# Power.net
KiCad netlist of a schematic drawn in Altium Designer
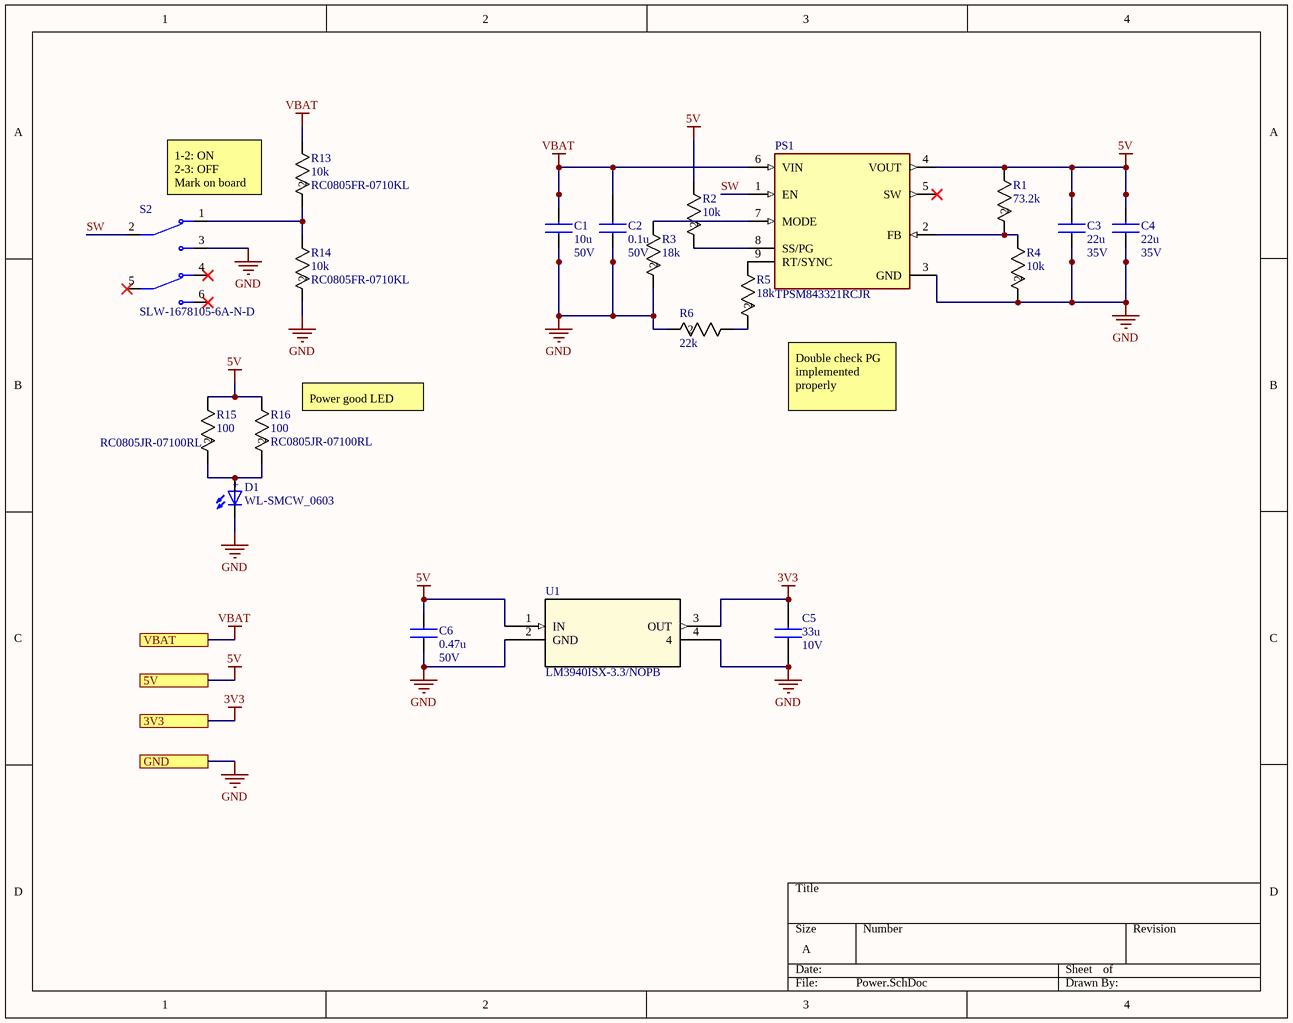
[diagram p0: Power.SchDoc]

(export (version "E")
  (design (tool "Eeschema 10.0.6"))
  (components
    (comp (ref "C1")
      (value "10u")
      (footprint "CAPC2012X145N")
      (description "Multilayer Ceramic Chip Capacitors, Capacitance=10?F, LxWxT:2x1.25x1.25mm")
      (fields
        (field (name "MOUSER PART NUMBER") "810-C2012X5R1H106K12")
        (field (name "MANUFACTURER_PART_NUMBER") "C2012X5R1H106K125AC")
        (field (name "RATED VOLTAGE") "50V")
      )
      (libsource (lib "Caps") (part "C2012X5R1H106K125AC"))
    )
    (comp (ref "C2")
      (value "0.1u")
      (footprint "CAPC2012X145N")
      (description "Multilayer Ceramic Chip Capacitors, Capacitance=0.1u")
      (fields
        (field (name "MANUFACTURER_PART_NUMBER") "KAM21BR71H104JM")
        (field (name "RATED VOLTAGE") "50V")
      )
      (libsource (lib "Caps") (part "KAM21BR71H104JM"))
    )
    (comp (ref "C3")
      (value "22u")
      (footprint "CAPC2012X145N")
      (description "Multilayer Ceramic Chip Capacitors, Capacitance=22u")
      (fields
        (field (name "MANUFACTURER_PART_NUMBER") "C2012X5R1V226M125AC")
        (field (name "RATED VOLTAGE") "35V")
      )
      (libsource (lib "Caps") (part "C2012X5R1V226M125AC"))
    )
    (comp (ref "C4")
      (value "22u")
      (footprint "CAPC2012X145N")
      (description "Multilayer Ceramic Chip Capacitors, Capacitance=22u")
      (fields
        (field (name "MANUFACTURER_PART_NUMBER") "C2012X5R1V226M125AC")
        (field (name "RATED VOLTAGE") "35V")
      )
      (libsource (lib "Caps") (part "C2012X5R1V226M125AC"))
    )
    (comp (ref "C5")
      (value "33u")
      (footprint "CAPC2012X145N")
      (description "Multilayer Ceramic Chip Capacitors, Capacitance=33u")
      (fields
        (field (name "MANUFACTURER_PART_NUMBER") "C2012X5R1A336M125AC")
        (field (name "RATED VOLTAGE") "10V")
      )
      (libsource (lib "Caps") (part "C2012X5R1A336M125AC"))
    )
    (comp (ref "C6")
      (value "0.47u")
      (footprint "CAPC2012X145N")
      (description "Multilayer Ceramic Chip Capacitors, Capacitance=0.47u")
      (fields
        (field (name "MANUFACTURER_PART_NUMBER") "GCM21BR71H474KA55K")
        (field (name "RATED VOLTAGE") "50V")
      )
      (libsource (lib "Caps") (part "GCM21BR71H474KA55K"))
    )
    (comp (ref "D1")
      (value "WL-SMCW_0603")
      (footprint "WL-SMCW_0603")
      (description "0603, Green Typ.(@20mA): 520nm, 430mcd, 3.2V, 140Â° InGaN")
      (fields (field (name "MF") "Wurth Electronics") (field (name "MP") "150060GS75000"))
      (libsource (lib "WL-SMCW_0603") (part "WL-SMCW_0603"))
    )
    (comp (ref "PS1")
      (value "TPSM843321RCJR")
      (footprint "MODULE_TPSM843321RCJR")
      (description "Non-Isolated PoL Module DC DC Converter 1 Output 5V 3A 3.8V - 18V Input")
      (fields (field (name "MF") "Texas Instruments"))
      (libsource (lib "TPSM843321RCJR") (part "TPSM843321RCJR"))
    )
    (comp (ref "R1")
      (value "73.2k")
      (footprint "RC0805N_YAG")
      (description "RES 0805 73.2k 1% 1/8W")
      (fields (field (name "MANUFACTURER_PART_NUMBER") "RC0805FR-0773K2L") (field (name "TOLERANCE") "1%"))
      (libsource (lib "Resistors") (part "RC0805FR-0773K2L"))
    )
    (comp (ref "R2")
      (value "10k")
      (footprint "RC0805N_YAG")
      (description "RES 0805 10k 1% 1/8W")
      (fields (field (name "MANUFACTURER_PART_NUMBER") "RC0805FR-0710KL") (field (name "TOLERANCE") "1%"))
      (libsource (lib "Resistors") (part "RC0805FR-0710KL"))
    )
    (comp (ref "R3")
      (value "18k")
      (footprint "RC0805N_YAG")
      (description "RES 0805 18k 1% 1/8W")
      (fields (field (name "MANUFACTURER_PART_NUMBER") "RC0805FR-0718KL") (field (name "TOLERANCE") "1%"))
      (libsource (lib "Resistors") (part "RC0805FR-0718KL"))
    )
    (comp (ref "R4")
      (value "10k")
      (footprint "RC0805N_YAG")
      (description "RES 0805 10k 1% 1/8W")
      (fields (field (name "MANUFACTURER_PART_NUMBER") "RC0805FR-0710KL") (field (name "TOLERANCE") "1%"))
      (libsource (lib "Resistors") (part "RC0805FR-0710KL"))
    )
    (comp (ref "R5")
      (value "18k")
      (footprint "RC0805N_YAG")
      (description "RES 0805 18k 1% 1/8W")
      (fields (field (name "MANUFACTURER_PART_NUMBER") "RC0805FR-0718KL") (field (name "TOLERANCE") "1%"))
      (libsource (lib "Resistors") (part "RC0805FR-0718KL"))
    )
    (comp (ref "R6")
      (value "22k")
      (footprint "RC0805N_YAG")
      (description "RES 0805 22k 1% 1/8W")
      (fields (field (name "MANUFACTURER_PART_NUMBER") "RC0805FR-0722KL") (field (name "TOLERANCE") "1%"))
      (libsource (lib "Resistors") (part "RC0805FR-0722KL"))
    )
    (comp (ref "R13")
      (value "RC0805FR-0710KL")
      (footprint "RC0805N_YAG")
      (description "RES 0805 10k 1% 1/8W")
      (fields (field (name "TOLERANCE") "1%") (field (name "ALTIUM_VALUE") "10k"))
      (libsource (lib "Resistors") (part "RC0805FR-0710KL"))
    )
    (comp (ref "R14")
      (value "RC0805FR-0710KL")
      (footprint "RC0805N_YAG")
      (description "RES 0805 10k 1% 1/8W")
      (fields (field (name "TOLERANCE") "1%") (field (name "ALTIUM_VALUE") "10k"))
      (libsource (lib "Resistors") (part "RC0805FR-0710KL"))
    )
    (comp (ref "R15")
      (value "RC0805JR-07100RL")
      (footprint "RC0805N_YAG")
      (description "RES 0805 100 5% 1/8W")
      (fields (field (name "TOLERANCE") "5%") (field (name "ALTIUM_VALUE") "100"))
      (libsource (lib "Resistors") (part "RC0805JR-07100RL"))
    )
    (comp (ref "R16")
      (value "RC0805JR-07100RL")
      (footprint "RC0805N_YAG")
      (description "RES 0805 100 5% 1/8W")
      (fields (field (name "TOLERANCE") "5%") (field (name "ALTIUM_VALUE") "100"))
      (libsource (lib "Resistors") (part "RC0805JR-07100RL"))
    )
    (comp (ref "S2")
      (value "SLW-1678105-6A-N-D")
      (footprint "SW_SLW-1678105-6A-N-D")
      (description "16 x 7.8 x 10.5 mm, 6 mm Raised Slide Actuator, Through Hole, Slide Switch")
      (fields (field (name "MF") "Same Sky"))
      (libsource (lib "SLW-1678105-6A-N-D") (part "SLW-1678105-6A-N-D"))
    )
    (comp (ref "U1")
      (value "LM3940ISX-3.3/NOPB")
      (footprint "TS3B")
      (description "1-A, low-dropout voltage regulator for 5-V to 3.3-V conversion 3-DDPAK/TO-263 -40 to 125")
      (fields (field (name "COPYRIGHT") "Copyright (C) 2025 Ultra Librarian. All rights reserved."))
      (libsource (lib "LM3940ISX-3P3NOPB") (part "LM3940ISX-3.3NOPB"))
    )
  )
  (nets
    (net (code "1") (name "/SW") (class "Default")
      (node (ref "PS1") (pin "1") (pinfunction "EN_1") (pintype "input"))
      (node (ref "S2") (pin "2") (pinfunction "2_2") (pintype "passive"))
    )
    (net (code "2") (name "3V3") (class "Default")
      (node (ref "C5") (pin "2") (pinfunction "2_2") (pintype "passive"))
      (node (ref "U1") (pin "3") (pinfunction "OUT_3") (pintype "output"))
    )
    (net (code "3") (name "5V") (class "Default")
      (node (ref "C3") (pin "2") (pinfunction "2_2") (pintype "passive"))
      (node (ref "C4") (pin "2") (pinfunction "2_2") (pintype "passive"))
      (node (ref "C6") (pin "2") (pinfunction "2_2") (pintype "passive"))
      (node (ref "PS1") (pin "4") (pinfunction "VOUT_4") (pintype "output"))
      (node (ref "R1") (pin "1") (pinfunction "1_1") (pintype "passive"))
      (node (ref "R15") (pin "1") (pinfunction "1_1") (pintype "passive"))
      (node (ref "R16") (pin "1") (pinfunction "1_1") (pintype "passive"))
      (node (ref "R2") (pin "1") (pinfunction "1_1") (pintype "passive"))
      (node (ref "U1") (pin "1") (pinfunction "IN_1") (pintype "input"))
    )
    (net (code "4") (name "GND") (class "Default")
      (node (ref "C1") (pin "1") (pinfunction "1_1") (pintype "passive"))
      (node (ref "C2") (pin "1") (pinfunction "1_1") (pintype "passive"))
      (node (ref "C3") (pin "1") (pinfunction "1_1") (pintype "passive"))
      (node (ref "C4") (pin "1") (pinfunction "1_1") (pintype "passive"))
      (node (ref "C5") (pin "1") (pinfunction "1_1") (pintype "passive"))
      (node (ref "C6") (pin "1") (pinfunction "1_1") (pintype "passive"))
      (node (ref "D1") (pin "1") (pinfunction "NEG_1") (pintype "passive"))
      (node (ref "PS1") (pin "3") (pinfunction "GND_3") (pintype "power_in"))
      (node (ref "R14") (pin "2") (pinfunction "2_2") (pintype "passive"))
      (node (ref "R3") (pin "2") (pinfunction "2_2") (pintype "passive"))
      (node (ref "R4") (pin "2") (pinfunction "2_2") (pintype "passive"))
      (node (ref "R6") (pin "2") (pinfunction "2_2") (pintype "passive"))
      (node (ref "S2") (pin "3") (pinfunction "3_3") (pintype "passive"))
      (node (ref "U1") (pin "2") (pinfunction "GND_2") (pintype "passive"))
      (node (ref "U1") (pin "4") (pinfunction "4_4") (pintype "passive"))
    )
    (net (code "5") (name "Net-(D1-POS)") (class "Default")
      (node (ref "D1") (pin "2") (pinfunction "POS_2") (pintype "passive"))
      (node (ref "R15") (pin "2") (pinfunction "2_2") (pintype "passive"))
      (node (ref "R16") (pin "2") (pinfunction "2_2") (pintype "passive"))
    )
    (net (code "6") (name "Net-(PS1-FB)") (class "Default")
      (node (ref "PS1") (pin "2") (pinfunction "FB_2") (pintype "input"))
      (node (ref "R1") (pin "2") (pinfunction "2_2") (pintype "passive"))
      (node (ref "R4") (pin "1") (pinfunction "1_1") (pintype "passive"))
    )
    (net (code "7") (name "Net-(PS1-MODE)") (class "Default")
      (node (ref "PS1") (pin "7") (pinfunction "MODE_7") (pintype "input"))
      (node (ref "R3") (pin "1") (pinfunction "1_1") (pintype "passive"))
    )
    (net (code "8") (name "Net-(PS1-RT{slash}SYNC)") (class "Default")
      (node (ref "PS1") (pin "9") (pinfunction "RT/SYNC_9") (pintype "passive"))
      (node (ref "R5") (pin "1") (pinfunction "1_1") (pintype "passive"))
    )
    (net (code "9") (name "Net-(PS1-SS{slash}PG)") (class "Default")
      (node (ref "PS1") (pin "8") (pinfunction "SS/PG_8") (pintype "passive"))
      (node (ref "R2") (pin "2") (pinfunction "2_2") (pintype "passive"))
    )
    (net (code "10") (name "Net-(R5-Pad2)") (class "Default")
      (node (ref "R5") (pin "2") (pinfunction "2_2") (pintype "passive"))
      (node (ref "R6") (pin "1") (pinfunction "1_1") (pintype "passive"))
    )
    (net (code "11") (name "Net-(R13-Pad2)") (class "Default")
      (node (ref "R13") (pin "2") (pinfunction "2_2") (pintype "passive"))
      (node (ref "R14") (pin "1") (pinfunction "1_1") (pintype "passive"))
      (node (ref "S2") (pin "1") (pinfunction "1_1") (pintype "passive"))
    )
    (net (code "12") (name "VBAT") (class "Default")
      (node (ref "C1") (pin "2") (pinfunction "2_2") (pintype "passive"))
      (node (ref "C2") (pin "2") (pinfunction "2_2") (pintype "passive"))
      (node (ref "PS1") (pin "6") (pinfunction "VIN_6") (pintype "input"))
      (node (ref "R13") (pin "1") (pinfunction "1_1") (pintype "passive"))
    )
    (net (code "13") (name "unconnected-(PS1-SW-Pad5)") (class "Default")
      (node (ref "PS1") (pin "5") (pinfunction "SW_5") (pintype "output+no_connect"))
    )
    (net (code "14") (name "unconnected-(S2-Pad4)") (class "Default")
      (node (ref "S2") (pin "4") (pinfunction "4_4") (pintype "passive+no_connect"))
    )
    (net (code "15") (name "unconnected-(S2-Pad5)") (class "Default")
      (node (ref "S2") (pin "5") (pinfunction "5_5") (pintype "passive+no_connect"))
    )
    (net (code "16") (name "unconnected-(S2-Pad6)") (class "Default")
      (node (ref "S2") (pin "6") (pinfunction "6_6") (pintype "passive+no_connect"))
    )
  )
)
